# H_Bridge.net
KiCad netlist of a schematic drawn in Altium Designer
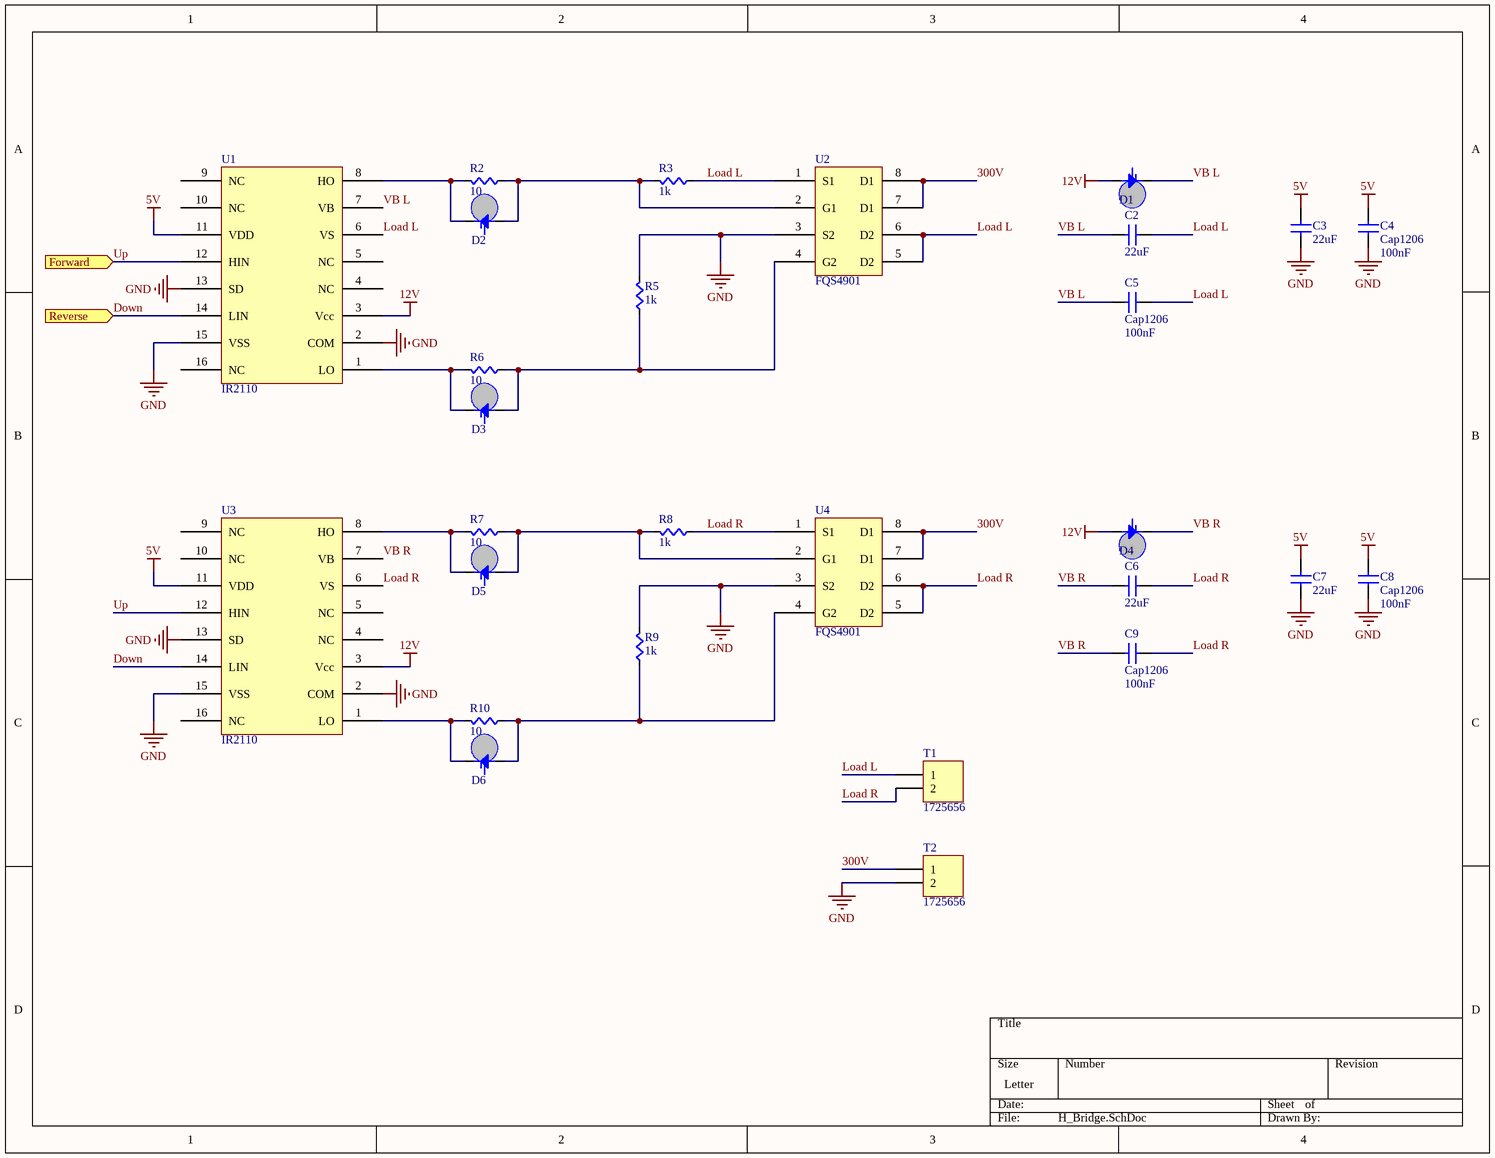
[diagram p0: H_Bridge.SchDoc]

(export (version "E")
  (design (tool "Eeschema 10.0.6"))
  (components
    (comp (ref "C2")
      (value "22uF")
      (footprint "CAPC0603")
      (fields (field (name "Comment") "Cap"))
      (libsource (lib "Passives") (part "Cap"))
    )
    (comp (ref "C3")
      (value "22uF")
      (footprint "CAPC0603")
      (fields (field (name "Comment") "Cap"))
      (libsource (lib "Passives") (part "Cap"))
    )
    (comp (ref "C4")
      (value "Cap1206")
      (footprint "CAP1206")
      (description "CAP CER 1UF 50V 10% X7R 1206")
      (fields (field (name "ALTIUM_VALUE") "100nF"))
      (libsource (lib "Passives") (part "Cap1206"))
    )
    (comp (ref "C5")
      (value "Cap1206")
      (footprint "CAP1206")
      (description "CAP CER 1UF 50V 10% X7R 1206")
      (fields (field (name "ALTIUM_VALUE") "100nF"))
      (libsource (lib "Passives") (part "Cap1206"))
    )
    (comp (ref "C6")
      (value "22uF")
      (footprint "CAPC0603")
      (fields (field (name "Comment") "Cap"))
      (libsource (lib "Passives") (part "Cap"))
    )
    (comp (ref "C7")
      (value "22uF")
      (footprint "CAPC0603")
      (fields (field (name "Comment") "Cap"))
      (libsource (lib "Passives") (part "Cap"))
    )
    (comp (ref "C8")
      (value "Cap1206")
      (footprint "CAP1206")
      (description "CAP CER 1UF 50V 10% X7R 1206")
      (fields (field (name "ALTIUM_VALUE") "100nF"))
      (libsource (lib "Passives") (part "Cap1206"))
    )
    (comp (ref "C9")
      (value "Cap1206")
      (footprint "CAP1206")
      (description "CAP CER 1UF 50V 10% X7R 1206")
      (fields (field (name "ALTIUM_VALUE") "100nF"))
      (libsource (lib "Passives") (part "Cap1206"))
    )
    (comp (ref "D1")
      (value "Diode")
      (footprint "TEMD5510FX01")
      (description "Standard Diode Template")
      (libsource (lib "Semiconductors") (part "Diode"))
    )
    (comp (ref "D2")
      (value "Diode")
      (footprint "TEMD5510FX01")
      (description "Standard Diode Template")
      (libsource (lib "") (part "Diode_1"))
    )
    (comp (ref "D3")
      (value "Diode")
      (footprint "TEMD5510FX01")
      (description "Standard Diode Template")
      (libsource (lib "") (part "Diode_1"))
    )
    (comp (ref "D4")
      (value "Diode")
      (footprint "TEMD5510FX01")
      (description "Standard Diode Template")
      (libsource (lib "Semiconductors") (part "Diode"))
    )
    (comp (ref "D5")
      (value "Diode")
      (footprint "TEMD5510FX01")
      (description "Standard Diode Template")
      (libsource (lib "") (part "Diode_1"))
    )
    (comp (ref "D6")
      (value "Diode")
      (footprint "TEMD5510FX01")
      (description "Standard Diode Template")
      (libsource (lib "") (part "Diode_1"))
    )
    (comp (ref "R2")
      (value "10")
      (footprint "RES0603")
      (fields (field (name "Comment") "Res"))
      (libsource (lib "Passives") (part "Res"))
    )
    (comp (ref "R3")
      (value "1k")
      (footprint "RES0603")
      (fields (field (name "Comment") "Res"))
      (libsource (lib "Passives") (part "Res"))
    )
    (comp (ref "R5")
      (value "1k")
      (footprint "RES0603")
      (fields (field (name "Comment") "Res"))
      (libsource (lib "Passives") (part "Res"))
    )
    (comp (ref "R6")
      (value "10")
      (footprint "RES0603")
      (fields (field (name "Comment") "Res"))
      (libsource (lib "Passives") (part "Res"))
    )
    (comp (ref "R7")
      (value "10")
      (footprint "RES0603")
      (fields (field (name "Comment") "Res"))
      (libsource (lib "Passives") (part "Res"))
    )
    (comp (ref "R8")
      (value "1k")
      (footprint "RES0603")
      (fields (field (name "Comment") "Res"))
      (libsource (lib "Passives") (part "Res"))
    )
    (comp (ref "R9")
      (value "1k")
      (footprint "RES0603")
      (fields (field (name "Comment") "Res"))
      (libsource (lib "Passives") (part "Res"))
    )
    (comp (ref "R10")
      (value "10")
      (footprint "RES0603")
      (fields (field (name "Comment") "Res"))
      (libsource (lib "Passives") (part "Res"))
    )
    (comp (ref "T1")
      (value "1725656")
      (footprint "1725656")
      (description "CONN TERM BLOCK 2.54MM 2POS")
      (libsource (lib "Sonar_Library") (part "1725656"))
    )
    (comp (ref "T2")
      (value "1725656")
      (footprint "1725656")
      (description "CONN TERM BLOCK 2.54MM 2POS")
      (libsource (lib "Sonar_Library") (part "1725656"))
    )
    (comp (ref "U1")
      (value "IR2110")
      (footprint "IR2110")
      (description "IC DRIVER HIGH/LOW SIDE 16SOIC")
      (libsource (lib "Sonar_Library") (part "IR2110"))
    )
    (comp (ref "U2")
      (value "FQS4901")
      (footprint "FQS4901")
      (description "MOSFET 2N-CH 400V 0.45A 8SOP")
      (libsource (lib "Sonar_Library") (part "FQS4901"))
    )
    (comp (ref "U3")
      (value "IR2110")
      (footprint "IR2110")
      (description "IC DRIVER HIGH/LOW SIDE 16SOIC")
      (libsource (lib "Sonar_Library") (part "IR2110"))
    )
    (comp (ref "U4")
      (value "FQS4901")
      (footprint "FQS4901")
      (description "MOSFET 2N-CH 400V 0.45A 8SOP")
      (libsource (lib "Sonar_Library") (part "FQS4901"))
    )
  )
  (nets
    (net (code "1") (name "/300V") (class "Default")
      (node (ref "T2") (pin "1") (pinfunction "1_1") (pintype "passive"))
      (node (ref "U2") (pin "7") (pinfunction "D1_7") (pintype "passive"))
      (node (ref "U2") (pin "8") (pinfunction "D1_8") (pintype "passive"))
      (node (ref "U4") (pin "7") (pinfunction "D1_7") (pintype "passive"))
      (node (ref "U4") (pin "8") (pinfunction "D1_8") (pintype "passive"))
    )
    (net (code "2") (name "/Down") (class "Default")
      (node (ref "U1") (pin "14") (pinfunction "LIN_14") (pintype "passive"))
      (node (ref "U3") (pin "14") (pinfunction "LIN_14") (pintype "passive"))
    )
    (net (code "3") (name "/Load L") (class "Default")
      (node (ref "C2") (pin "1") (pinfunction "A_1") (pintype "passive"))
      (node (ref "C5") (pin "1") (pinfunction "A_1") (pintype "passive"))
      (node (ref "R3") (pin "2") (pinfunction "B_2") (pintype "passive"))
      (node (ref "T1") (pin "1") (pinfunction "1_1") (pintype "passive"))
      (node (ref "U1") (pin "6") (pinfunction "VS_6") (pintype "passive"))
      (node (ref "U2") (pin "1") (pinfunction "S1_1") (pintype "passive"))
      (node (ref "U2") (pin "5") (pinfunction "D2_5") (pintype "passive"))
      (node (ref "U2") (pin "6") (pinfunction "D2_6") (pintype "passive"))
    )
    (net (code "4") (name "/Load R") (class "Default")
      (node (ref "C6") (pin "1") (pinfunction "A_1") (pintype "passive"))
      (node (ref "C9") (pin "1") (pinfunction "A_1") (pintype "passive"))
      (node (ref "R8") (pin "2") (pinfunction "B_2") (pintype "passive"))
      (node (ref "T1") (pin "2") (pinfunction "2_2") (pintype "passive"))
      (node (ref "U3") (pin "6") (pinfunction "VS_6") (pintype "passive"))
      (node (ref "U4") (pin "1") (pinfunction "S1_1") (pintype "passive"))
      (node (ref "U4") (pin "5") (pinfunction "D2_5") (pintype "passive"))
      (node (ref "U4") (pin "6") (pinfunction "D2_6") (pintype "passive"))
    )
    (net (code "5") (name "/Up") (class "Default")
      (node (ref "U1") (pin "12") (pinfunction "HIN_12") (pintype "passive"))
      (node (ref "U3") (pin "12") (pinfunction "HIN_12") (pintype "passive"))
    )
    (net (code "6") (name "/VB L") (class "Default")
      (node (ref "C2") (pin "2") (pinfunction "B_2") (pintype "passive"))
      (node (ref "C5") (pin "2") (pinfunction "B_2") (pintype "passive"))
      (node (ref "D1") (pin "C") (pinfunction "C_C") (pintype "passive"))
      (node (ref "U1") (pin "7") (pinfunction "VB_7") (pintype "passive"))
    )
    (net (code "7") (name "/VB R") (class "Default")
      (node (ref "C6") (pin "2") (pinfunction "B_2") (pintype "passive"))
      (node (ref "C9") (pin "2") (pinfunction "B_2") (pintype "passive"))
      (node (ref "D4") (pin "C") (pinfunction "C_C") (pintype "passive"))
      (node (ref "U3") (pin "7") (pinfunction "VB_7") (pintype "passive"))
    )
    (net (code "8") (name "5V") (class "Default")
      (node (ref "C3") (pin "2") (pinfunction "B_2") (pintype "passive"))
      (node (ref "C4") (pin "2") (pinfunction "B_2") (pintype "passive"))
      (node (ref "C7") (pin "2") (pinfunction "B_2") (pintype "passive"))
      (node (ref "C8") (pin "2") (pinfunction "B_2") (pintype "passive"))
      (node (ref "U1") (pin "11") (pinfunction "VDD_11") (pintype "passive"))
      (node (ref "U3") (pin "11") (pinfunction "VDD_11") (pintype "passive"))
    )
    (net (code "9") (name "12V") (class "Default")
      (node (ref "D1") (pin "A") (pinfunction "A_A") (pintype "passive"))
      (node (ref "D4") (pin "A") (pinfunction "A_A") (pintype "passive"))
      (node (ref "U1") (pin "3") (pinfunction "Vcc_3") (pintype "passive"))
      (node (ref "U3") (pin "3") (pinfunction "Vcc_3") (pintype "passive"))
    )
    (net (code "10") (name "GND") (class "Default")
      (node (ref "C3") (pin "1") (pinfunction "A_1") (pintype "passive"))
      (node (ref "C4") (pin "1") (pinfunction "A_1") (pintype "passive"))
      (node (ref "C7") (pin "1") (pinfunction "A_1") (pintype "passive"))
      (node (ref "C8") (pin "1") (pinfunction "A_1") (pintype "passive"))
      (node (ref "R5") (pin "1") (pinfunction "A_1") (pintype "passive"))
      (node (ref "R9") (pin "1") (pinfunction "A_1") (pintype "passive"))
      (node (ref "T2") (pin "2") (pinfunction "2_2") (pintype "passive"))
      (node (ref "U1") (pin "13") (pinfunction "SD_13") (pintype "passive"))
      (node (ref "U1") (pin "15") (pinfunction "VSS_15") (pintype "passive"))
      (node (ref "U1") (pin "2") (pinfunction "COM_2") (pintype "passive"))
      (node (ref "U2") (pin "3") (pinfunction "S2_3") (pintype "passive"))
      (node (ref "U3") (pin "13") (pinfunction "SD_13") (pintype "passive"))
      (node (ref "U3") (pin "15") (pinfunction "VSS_15") (pintype "passive"))
      (node (ref "U3") (pin "2") (pinfunction "COM_2") (pintype "passive"))
      (node (ref "U4") (pin "3") (pinfunction "S2_3") (pintype "passive"))
    )
    (net (code "11") (name "Net-(R2-A)") (class "Default")
      (node (ref "D2") (pin "C") (pinfunction "C_C") (pintype "passive"))
      (node (ref "R2") (pin "1") (pinfunction "A_1") (pintype "passive"))
      (node (ref "U1") (pin "8") (pinfunction "HO_8") (pintype "passive"))
    )
    (net (code "12") (name "Net-(R2-B)") (class "Default")
      (node (ref "D2") (pin "A") (pinfunction "A_A") (pintype "passive"))
      (node (ref "R2") (pin "2") (pinfunction "B_2") (pintype "passive"))
      (node (ref "R3") (pin "1") (pinfunction "A_1") (pintype "passive"))
      (node (ref "U2") (pin "2") (pinfunction "G1_2") (pintype "passive"))
    )
    (net (code "13") (name "Net-(R5-B)") (class "Default")
      (node (ref "D3") (pin "A") (pinfunction "A_A") (pintype "passive"))
      (node (ref "R5") (pin "2") (pinfunction "B_2") (pintype "passive"))
      (node (ref "R6") (pin "2") (pinfunction "B_2") (pintype "passive"))
      (node (ref "U2") (pin "4") (pinfunction "G2_4") (pintype "passive"))
    )
    (net (code "14") (name "Net-(R6-A)") (class "Default")
      (node (ref "D3") (pin "C") (pinfunction "C_C") (pintype "passive"))
      (node (ref "R6") (pin "1") (pinfunction "A_1") (pintype "passive"))
      (node (ref "U1") (pin "1") (pinfunction "LO_1") (pintype "passive"))
    )
    (net (code "15") (name "Net-(R7-A)") (class "Default")
      (node (ref "D5") (pin "C") (pinfunction "C_C") (pintype "passive"))
      (node (ref "R7") (pin "1") (pinfunction "A_1") (pintype "passive"))
      (node (ref "U3") (pin "8") (pinfunction "HO_8") (pintype "passive"))
    )
    (net (code "16") (name "Net-(R7-B)") (class "Default")
      (node (ref "D5") (pin "A") (pinfunction "A_A") (pintype "passive"))
      (node (ref "R7") (pin "2") (pinfunction "B_2") (pintype "passive"))
      (node (ref "R8") (pin "1") (pinfunction "A_1") (pintype "passive"))
      (node (ref "U4") (pin "2") (pinfunction "G1_2") (pintype "passive"))
    )
    (net (code "17") (name "Net-(R10-A)") (class "Default")
      (node (ref "D6") (pin "C") (pinfunction "C_C") (pintype "passive"))
      (node (ref "R10") (pin "1") (pinfunction "A_1") (pintype "passive"))
      (node (ref "U3") (pin "1") (pinfunction "LO_1") (pintype "passive"))
    )
    (net (code "18") (name "Net-(R10-B)") (class "Default")
      (node (ref "D6") (pin "A") (pinfunction "A_A") (pintype "passive"))
      (node (ref "R10") (pin "2") (pinfunction "B_2") (pintype "passive"))
      (node (ref "R9") (pin "2") (pinfunction "B_2") (pintype "passive"))
      (node (ref "U4") (pin "4") (pinfunction "G2_4") (pintype "passive"))
    )
    (net (code "19") (name "unconnected-(U1-NC-Pad4)") (class "Default")
      (node (ref "U1") (pin "4") (pinfunction "NC_4") (pintype "passive"))
    )
    (net (code "20") (name "unconnected-(U1-NC-Pad5)") (class "Default")
      (node (ref "U1") (pin "5") (pinfunction "NC_5") (pintype "passive"))
    )
    (net (code "21") (name "unconnected-(U1-NC-Pad9)") (class "Default")
      (node (ref "U1") (pin "9") (pinfunction "NC_9") (pintype "passive"))
    )
    (net (code "22") (name "unconnected-(U1-NC-Pad10)") (class "Default")
      (node (ref "U1") (pin "10") (pinfunction "NC_10") (pintype "passive"))
    )
    (net (code "23") (name "unconnected-(U1-NC-Pad16)") (class "Default")
      (node (ref "U1") (pin "16") (pinfunction "NC_16") (pintype "passive"))
    )
    (net (code "24") (name "unconnected-(U3-NC-Pad4)") (class "Default")
      (node (ref "U3") (pin "4") (pinfunction "NC_4") (pintype "passive"))
    )
    (net (code "25") (name "unconnected-(U3-NC-Pad5)") (class "Default")
      (node (ref "U3") (pin "5") (pinfunction "NC_5") (pintype "passive"))
    )
    (net (code "26") (name "unconnected-(U3-NC-Pad9)") (class "Default")
      (node (ref "U3") (pin "9") (pinfunction "NC_9") (pintype "passive"))
    )
    (net (code "27") (name "unconnected-(U3-NC-Pad10)") (class "Default")
      (node (ref "U3") (pin "10") (pinfunction "NC_10") (pintype "passive"))
    )
    (net (code "28") (name "unconnected-(U3-NC-Pad16)") (class "Default")
      (node (ref "U3") (pin "16") (pinfunction "NC_16") (pintype "passive"))
    )
  )
)
